# stm32_lin_router.net
KiCad netlist of a schematic drawn in EasyEDA Pro
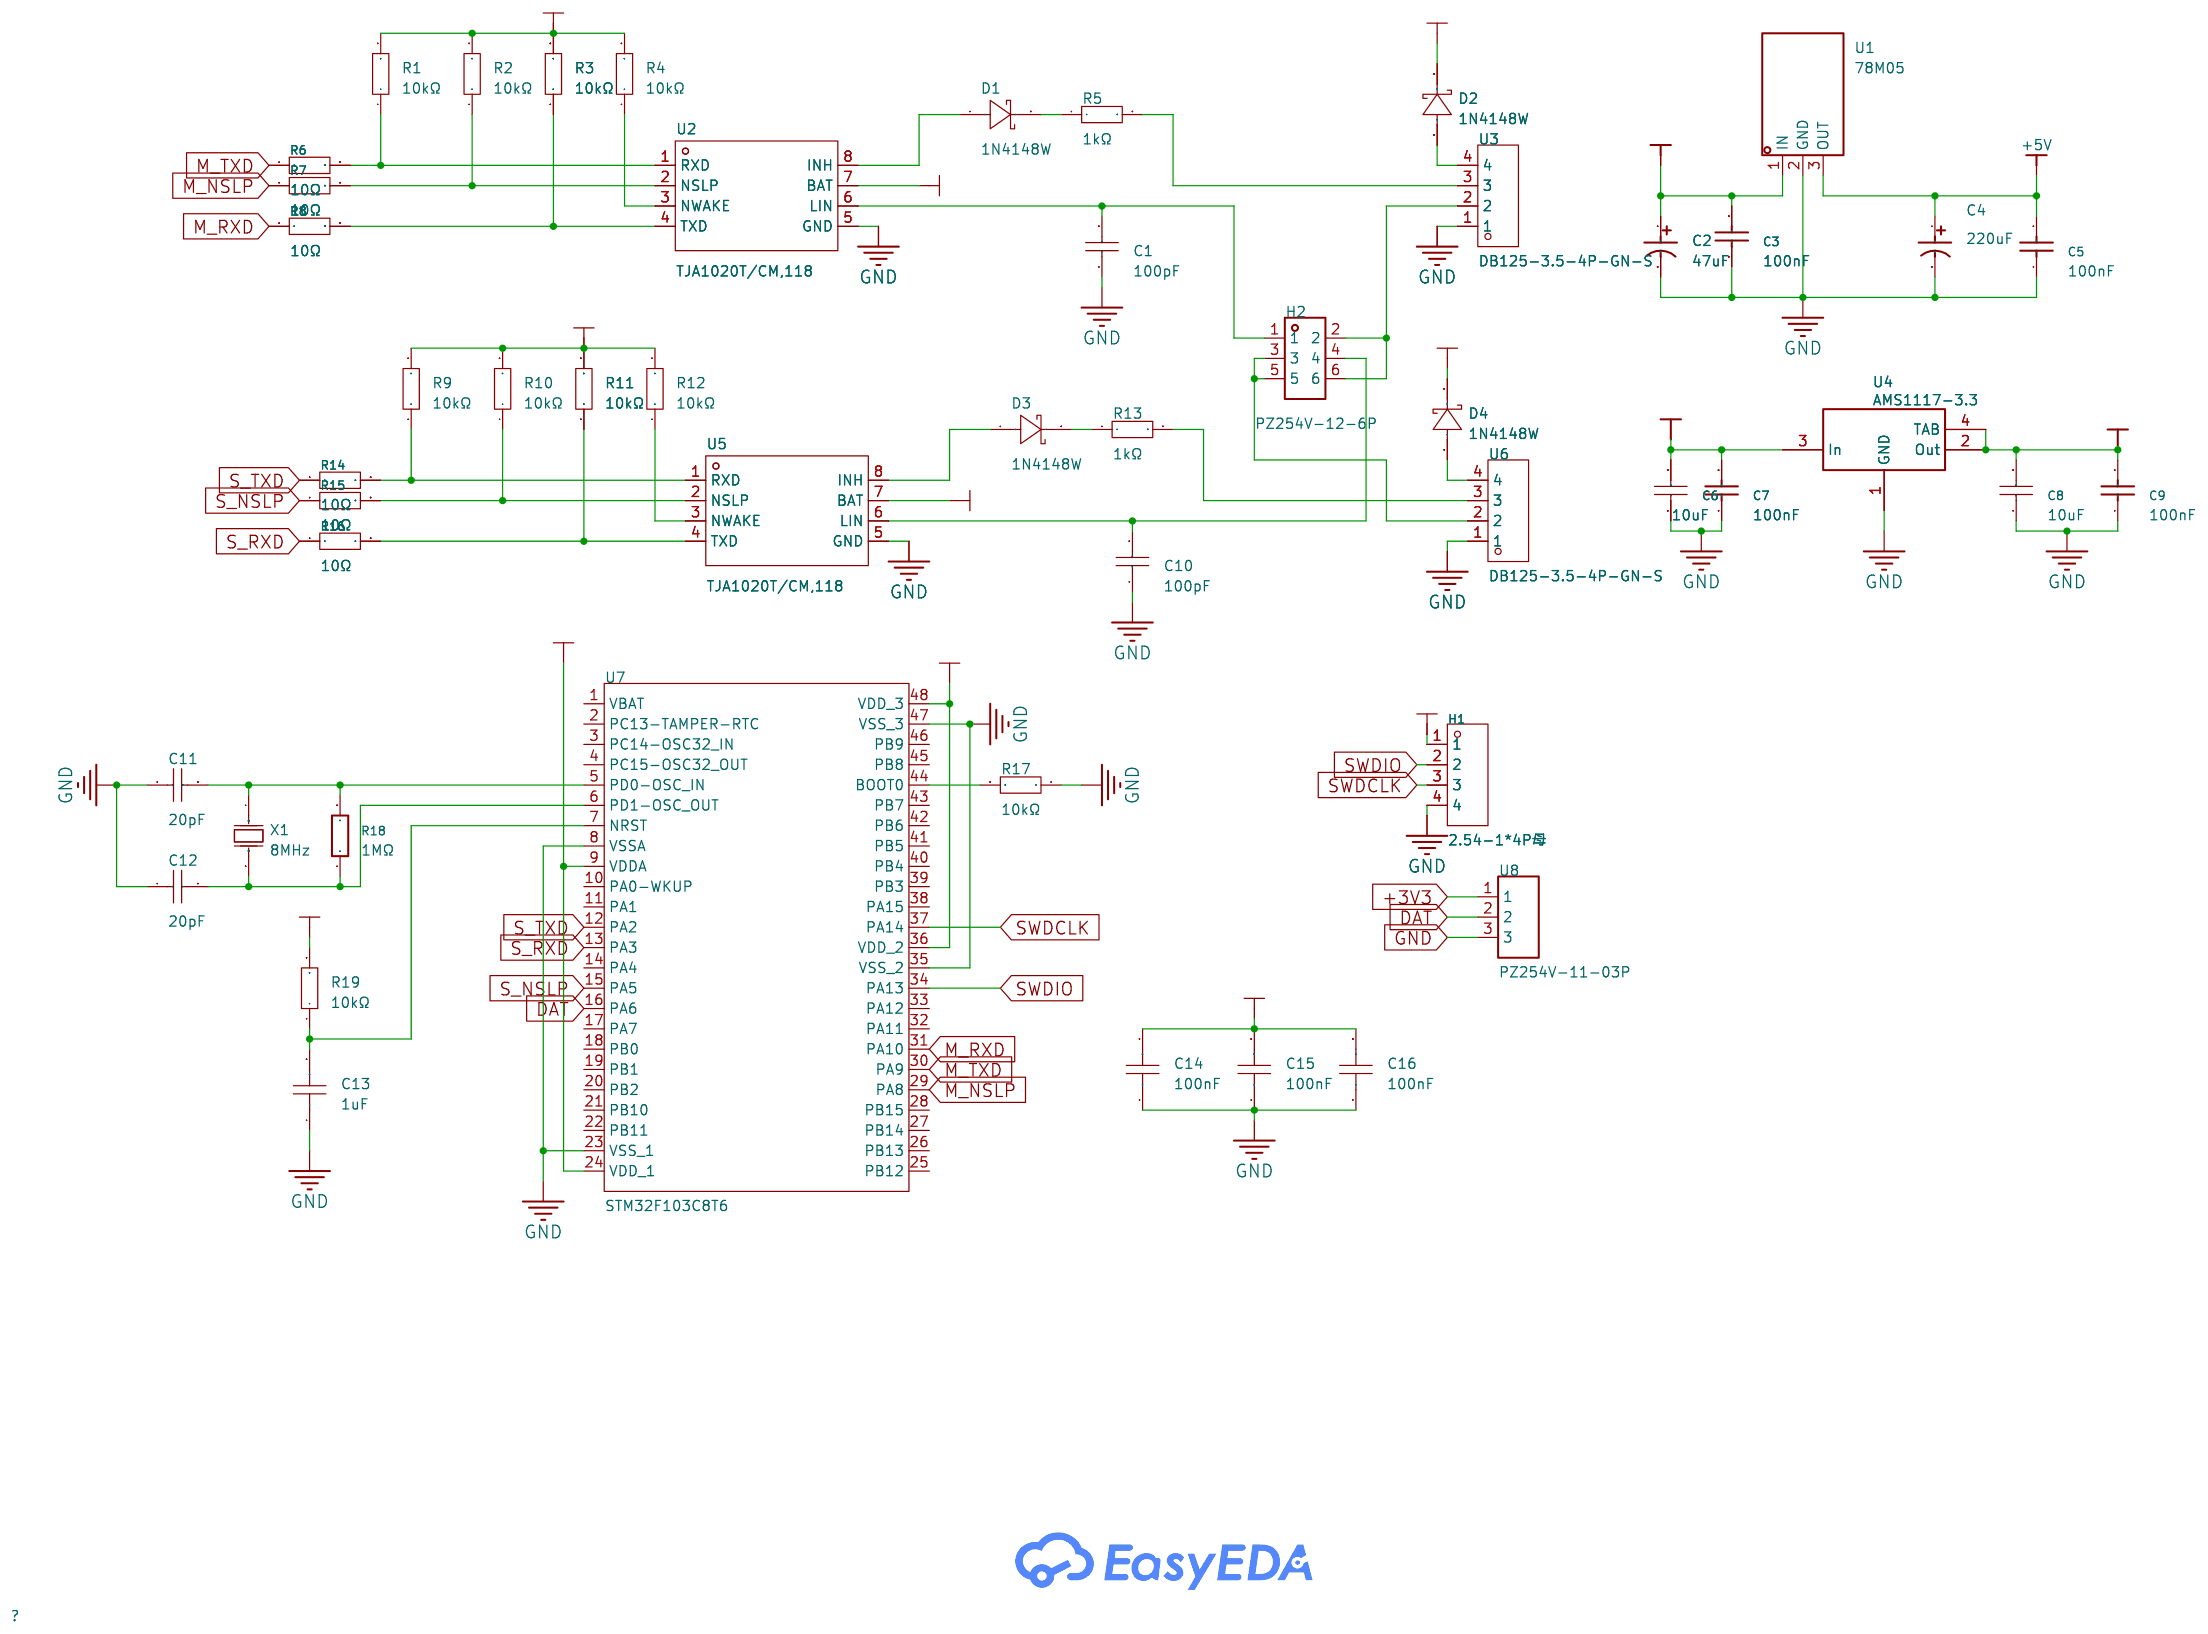
[diagram p0: schematic sheet]

(export (version "E")
  (design (tool "Eeschema 10.0.6"))
  (components
    (comp (ref "C1")
      (value "100pF")
      (description "Capacitance:100pF Tolerance:±5% Tolerance:±5% Voltage Rating:50V Temperature Coefficient:C0G")
      (fields (field (name "Manufacturer Part") "0402CG101J500NT") (field (name "Manufacturer") "FH(风华)"))
      (libsource (lib "easyedapro") (part "0402CG101J500NT"))
    )
    (comp (ref "C2")
      (value "47uF")
      (footprint "easyedapro:CAP-SMD_BD6.3-L6.6-W6.6-FD")
      (fields (field (name "Manufacturer Part") "RVT1V470M0605") (field (name "Manufacturer") "ROQANG(容强)"))
      (libsource (lib "easyedapro") (part "RVT1V470M0605_c72522"))
    )
    (comp (ref "C3")
      (value "100nF")
      (footprint "easyedapro:C0402")
      (fields
        (field (name "Manufacturer Part") "CC0402KRX7R9BB104")
        (field (name "Manufacturer") "YAGEO(国巨)")
      )
      (libsource (lib "easyedapro") (part "CC0402KRX7R9BB104"))
    )
    (comp (ref "C4")
      (value "220uF")
      (footprint "easyedapro:CAP-SMD_BD6.3-L6.6-W6.6-FD")
      (fields (field (name "Manufacturer Part") "RVT1A221M0605") (field (name "Manufacturer") "ROQANG(容强)"))
      (libsource (lib "easyedapro") (part "RVT1A221M0605-C72494"))
    )
    (comp (ref "C5")
      (value "100nF")
      (footprint "easyedapro:C0402")
      (fields
        (field (name "Manufacturer Part") "CC0402KRX7R9BB104")
        (field (name "Manufacturer") "YAGEO(国巨)")
      )
      (libsource (lib "easyedapro") (part "CC0402KRX7R9BB104"))
    )
    (comp (ref "C6")
      (value "10uF")
      (footprint "easyedapro:C0603")
      (description "Capacitance:10uF Tolerance:±20% Tolerance:±20% Voltage Rating:16V Temperature Coefficient:X5R")
      (fields
        (field (name "Manufacturer Part") "CL10A106MO8NQNC")
        (field (name "Manufacturer") "SAMSUNG(三星)")
      )
      (libsource (lib "easyedapro") (part "CL10A106MO8NQNC"))
    )
    (comp (ref "C7")
      (value "100nF")
      (footprint "easyedapro:C0402")
      (fields
        (field (name "Manufacturer Part") "CC0402KRX7R9BB104")
        (field (name "Manufacturer") "YAGEO(国巨)")
      )
      (libsource (lib "easyedapro") (part "CC0402KRX7R9BB104"))
    )
    (comp (ref "C8")
      (value "10uF")
      (footprint "easyedapro:C0603")
      (description "Capacitance:10uF Tolerance:±20% Tolerance:±20% Voltage Rating:16V Temperature Coefficient:X5R")
      (fields
        (field (name "Manufacturer Part") "CL10A106MO8NQNC")
        (field (name "Manufacturer") "SAMSUNG(三星)")
      )
      (libsource (lib "easyedapro") (part "CL10A106MO8NQNC"))
    )
    (comp (ref "C9")
      (value "100nF")
      (footprint "easyedapro:C0402")
      (fields
        (field (name "Manufacturer Part") "CC0402KRX7R9BB104")
        (field (name "Manufacturer") "YAGEO(国巨)")
      )
      (libsource (lib "easyedapro") (part "CC0402KRX7R9BB104"))
    )
    (comp (ref "C10")
      (value "100pF")
      (description "Capacitance:100pF Tolerance:±5% Tolerance:±5% Voltage Rating:50V Temperature Coefficient:C0G")
      (fields (field (name "Manufacturer Part") "0402CG101J500NT") (field (name "Manufacturer") "FH(风华)"))
      (libsource (lib "easyedapro") (part "0402CG101J500NT"))
    )
    (comp (ref "C11")
      (value "20pF")
      (footprint "easyedapro:C0402")
      (description "Capacitance:20pF Tolerance:±5% Tolerance:±5% Voltage Rating:50V Temperature Coefficient:C0G")
      (fields (field (name "Manufacturer Part") "0402CG200J500NT") (field (name "Manufacturer") "FH(风华)"))
      (libsource (lib "easyedapro") (part "0402CG200J500NT"))
    )
    (comp (ref "C12")
      (value "20pF")
      (footprint "easyedapro:C0402")
      (description "Capacitance:20pF Tolerance:±5% Tolerance:±5% Voltage Rating:50V Temperature Coefficient:C0G")
      (fields (field (name "Manufacturer Part") "0402CG200J500NT") (field (name "Manufacturer") "FH(风华)"))
      (libsource (lib "easyedapro") (part "0402CG200J500NT"))
    )
    (comp (ref "C13")
      (value "1uF")
      (footprint "easyedapro:C0402")
      (description "Capacitance:1uF Tolerance:±10% Tolerance:±10% Voltage Rating:25V Temperature Coefficient:X5R")
      (fields
        (field (name "Manufacturer Part") "CL05A105KA5NQNC")
        (field (name "Manufacturer") "SAMSUNG(三星)")
      )
      (libsource (lib "easyedapro") (part "CL05A105KA5NQNC"))
    )
    (comp (ref "C14")
      (value "100nF")
      (footprint "easyedapro:C0402")
      (description "Capacitance:100nF Tolerance:±10% Tolerance:±10% Voltage Rating:16V Temperature Coefficient:X7R")
      (fields
        (field (name "Manufacturer Part") "CL05B104KO5NNNC")
        (field (name "Manufacturer") "SAMSUNG(三星)")
      )
      (libsource (lib "easyedapro") (part "CL05B104KO5NNNC"))
    )
    (comp (ref "C15")
      (value "100nF")
      (footprint "easyedapro:C0402")
      (description "Capacitance:100nF Tolerance:±10% Tolerance:±10% Voltage Rating:16V Temperature Coefficient:X7R")
      (fields
        (field (name "Manufacturer Part") "CL05B104KO5NNNC")
        (field (name "Manufacturer") "SAMSUNG(三星)")
      )
      (libsource (lib "easyedapro") (part "CL05B104KO5NNNC"))
    )
    (comp (ref "C16")
      (value "100nF")
      (footprint "easyedapro:C0402")
      (description "Capacitance:100nF Tolerance:±10% Tolerance:±10% Voltage Rating:16V Temperature Coefficient:X7R")
      (fields
        (field (name "Manufacturer Part") "CL05B104KO5NNNC")
        (field (name "Manufacturer") "SAMSUNG(三星)")
      )
      (libsource (lib "easyedapro") (part "CL05B104KO5NNNC"))
    )
    (comp (ref "D1")
      (value "1N4148W")
      (footprint "easyedapro:SOD-123_L2.7-W1.6-LS3.7-FD")
      (fields (field (name "Manufacturer") "R+O(宏嘉诚)"))
      (libsource (lib "easyedapro") (part "1N4148W_C7420318"))
    )
    (comp (ref "D2")
      (value "1N4148W")
      (footprint "easyedapro:SOD-123_L2.7-W1.6-LS3.7-FD")
      (fields (field (name "Manufacturer") "R+O(宏嘉诚)"))
      (libsource (lib "easyedapro") (part "1N4148W_C7420318"))
    )
    (comp (ref "D3")
      (value "1N4148W")
      (footprint "easyedapro:SOD-123_L2.7-W1.6-LS3.7-FD")
      (fields (field (name "Manufacturer") "R+O(宏嘉诚)"))
      (libsource (lib "easyedapro") (part "1N4148W_C7420318"))
    )
    (comp (ref "D4")
      (value "1N4148W")
      (footprint "easyedapro:SOD-123_L2.7-W1.6-LS3.7-FD")
      (fields (field (name "Manufacturer") "R+O(宏嘉诚)"))
      (libsource (lib "easyedapro") (part "1N4148W_C7420318"))
    )
    (comp (ref "H1")
      (value "2.54-1*4P母")
      (footprint "easyedapro:HDR-TH_4P-P2.54-V-F")
      (fields (field (name "Manufacturer") "BOOMELE(博穆精密)"))
      (libsource (lib "easyedapro") (part "2.54-1*4P母"))
    )
    (comp (ref "H2")
      (value "PZ254V-12-6P")
      (footprint "easyedapro:HDR-TH_6P-P2.54-V-M-R2-C3-S2.54")
      (fields (field (name "Manufacturer") "XFCN(兴飞)"))
      (libsource (lib "easyedapro") (part "PZ254V-12-6P"))
    )
    (comp (ref "R1")
      (value "10kΩ")
      (footprint "easyedapro:R0402")
      (fields
        (field (name "Manufacturer Part") "0402WGF1002TCE")
        (field (name "Manufacturer") "UNI-ROYAL(厚声)")
      )
      (libsource (lib "easyedapro") (part "0402WGF1002TCE"))
    )
    (comp (ref "R2")
      (value "10kΩ")
      (footprint "easyedapro:R0402")
      (fields
        (field (name "Manufacturer Part") "0402WGF1002TCE")
        (field (name "Manufacturer") "UNI-ROYAL(厚声)")
      )
      (libsource (lib "easyedapro") (part "0402WGF1002TCE"))
    )
    (comp (ref "R3")
      (value "10kΩ")
      (footprint "easyedapro:R0402")
      (fields
        (field (name "Manufacturer Part") "0402WGF1002TCE")
        (field (name "Manufacturer") "UNI-ROYAL(厚声)")
      )
      (libsource (lib "easyedapro") (part "0402WGF1002TCE"))
    )
    (comp (ref "R4")
      (value "10kΩ")
      (footprint "easyedapro:R0402")
      (fields
        (field (name "Manufacturer Part") "0402WGF1002TCE")
        (field (name "Manufacturer") "UNI-ROYAL(厚声)")
      )
      (libsource (lib "easyedapro") (part "0402WGF1002TCE"))
    )
    (comp (ref "R5")
      (value "1kΩ")
      (footprint "easyedapro:R0402")
      (fields
        (field (name "Manufacturer Part") "0402WGF1001TCE")
        (field (name "Manufacturer") "UNI-ROYAL(厚声)")
      )
      (libsource (lib "easyedapro") (part "0402WGF1001TCE"))
    )
    (comp (ref "R6")
      (value "10Ω")
      (footprint "easyedapro:R0402")
      (fields
        (field (name "Manufacturer Part") "0402WGF100JTCE")
        (field (name "Manufacturer") "UNI-ROYAL(厚声)")
      )
      (libsource (lib "easyedapro") (part "0402WGF100JTCE"))
    )
    (comp (ref "R7")
      (value "10Ω")
      (footprint "easyedapro:R0402")
      (fields
        (field (name "Manufacturer Part") "0402WGF100JTCE")
        (field (name "Manufacturer") "UNI-ROYAL(厚声)")
      )
      (libsource (lib "easyedapro") (part "0402WGF100JTCE"))
    )
    (comp (ref "R8")
      (value "10Ω")
      (footprint "easyedapro:R0402")
      (fields
        (field (name "Manufacturer Part") "0402WGF100JTCE")
        (field (name "Manufacturer") "UNI-ROYAL(厚声)")
      )
      (libsource (lib "easyedapro") (part "0402WGF100JTCE"))
    )
    (comp (ref "R9")
      (value "10kΩ")
      (footprint "easyedapro:R0402")
      (fields
        (field (name "Manufacturer Part") "0402WGF1002TCE")
        (field (name "Manufacturer") "UNI-ROYAL(厚声)")
      )
      (libsource (lib "easyedapro") (part "0402WGF1002TCE"))
    )
    (comp (ref "R10")
      (value "10kΩ")
      (footprint "easyedapro:R0402")
      (fields
        (field (name "Manufacturer Part") "0402WGF1002TCE")
        (field (name "Manufacturer") "UNI-ROYAL(厚声)")
      )
      (libsource (lib "easyedapro") (part "0402WGF1002TCE"))
    )
    (comp (ref "R11")
      (value "10kΩ")
      (footprint "easyedapro:R0402")
      (fields
        (field (name "Manufacturer Part") "0402WGF1002TCE")
        (field (name "Manufacturer") "UNI-ROYAL(厚声)")
      )
      (libsource (lib "easyedapro") (part "0402WGF1002TCE"))
    )
    (comp (ref "R12")
      (value "10kΩ")
      (footprint "easyedapro:R0402")
      (fields
        (field (name "Manufacturer Part") "0402WGF1002TCE")
        (field (name "Manufacturer") "UNI-ROYAL(厚声)")
      )
      (libsource (lib "easyedapro") (part "0402WGF1002TCE"))
    )
    (comp (ref "R13")
      (value "1kΩ")
      (footprint "easyedapro:R0402")
      (fields
        (field (name "Manufacturer Part") "0402WGF1001TCE")
        (field (name "Manufacturer") "UNI-ROYAL(厚声)")
      )
      (libsource (lib "easyedapro") (part "0402WGF1001TCE"))
    )
    (comp (ref "R14")
      (value "10Ω")
      (footprint "easyedapro:R0402")
      (fields
        (field (name "Manufacturer Part") "0402WGF100JTCE")
        (field (name "Manufacturer") "UNI-ROYAL(厚声)")
      )
      (libsource (lib "easyedapro") (part "0402WGF100JTCE"))
    )
    (comp (ref "R15")
      (value "10Ω")
      (footprint "easyedapro:R0402")
      (fields
        (field (name "Manufacturer Part") "0402WGF100JTCE")
        (field (name "Manufacturer") "UNI-ROYAL(厚声)")
      )
      (libsource (lib "easyedapro") (part "0402WGF100JTCE"))
    )
    (comp (ref "R16")
      (value "10Ω")
      (footprint "easyedapro:R0402")
      (fields
        (field (name "Manufacturer Part") "0402WGF100JTCE")
        (field (name "Manufacturer") "UNI-ROYAL(厚声)")
      )
      (libsource (lib "easyedapro") (part "0402WGF100JTCE"))
    )
    (comp (ref "R17")
      (value "10kΩ")
      (footprint "easyedapro:R0402")
      (fields
        (field (name "Manufacturer Part") "0402WGF1002TCE")
        (field (name "Manufacturer") "UNI-ROYAL(厚声)")
      )
      (libsource (lib "easyedapro") (part "0402WGF1002TCE"))
    )
    (comp (ref "R18")
      (value "1MΩ")
      (footprint "easyedapro:R0402")
      (fields
        (field (name "Manufacturer Part") "0402WGF1004TCE")
        (field (name "Manufacturer") "UNI-ROYAL(厚声)")
      )
      (libsource (lib "easyedapro") (part "0402WGF1004TCE"))
    )
    (comp (ref "R19")
      (value "10kΩ")
      (footprint "easyedapro:R0402")
      (fields
        (field (name "Manufacturer Part") "0402WGF1002TCE")
        (field (name "Manufacturer") "UNI-ROYAL(厚声)")
      )
      (libsource (lib "easyedapro") (part "0402WGF1002TCE"))
    )
    (comp (ref "U1")
      (value "78M05")
      (footprint "easyedapro:TO-252-2_L6.6-W6.1-P4.57-LS9.9-BR-CW")
      (fields (field (name "Manufacturer") "UMW(友台半导体)"))
      (libsource (lib "easyedapro") (part "UMW78M05"))
    )
    (comp (ref "U2")
      (value "TJA1020T/CM,118")
      (fields (field (name "Manufacturer") "NXP(恩智浦)"))
      (libsource (lib "easyedapro") (part "TJA1020T/CM,118"))
    )
    (comp (ref "U3")
      (value "DB125-3.5-4P-GN-S")
      (footprint "easyedapro:CONN-TH_DB125-3.5-4P-GN")
      (fields (field (name "Manufacturer") "DORABO(地博电气)"))
      (libsource (lib "easyedapro") (part "DB125-3.5-4P-GN"))
    )
    (comp (ref "U4")
      (value "AMS1117-3.3")
      (fields (field (name "Manufacturer") "AMS"))
      (libsource (lib "easyedapro") (part "AMS1117-3.3"))
    )
    (comp (ref "U5")
      (value "TJA1020T/CM,118")
      (fields (field (name "Manufacturer") "NXP(恩智浦)"))
      (libsource (lib "easyedapro") (part "TJA1020T/CM,118"))
    )
    (comp (ref "U6")
      (value "DB125-3.5-4P-GN-S")
      (footprint "easyedapro:CONN-TH_DB125-3.5-4P-GN")
      (fields (field (name "Manufacturer") "DORABO(地博电气)"))
      (libsource (lib "easyedapro") (part "DB125-3.5-4P-GN"))
    )
    (comp (ref "U7")
      (value "STM32F103C8T6")
      (footprint "easyedapro:LQFP-48_L7.0-W7.0-P0.50-LS9.0-BL")
      (fields (field (name "Manufacturer") "ST(意法半导体)"))
      (libsource (lib "easyedapro") (part "STM32F103C8T6"))
    )
    (comp (ref "U8")
      (value "PZ254V-11-03P")
      (footprint "easyedapro:HDR-TH_3P-P2.54-V-M")
      (fields (field (name "Manufacturer") "XFCN(兴飞)"))
      (libsource (lib "easyedapro") (part "PZ254V-11-03P_C2937625"))
    )
    (comp (ref "X1")
      (value "8MHz")
      (footprint "easyedapro:CRYSTAL-SMD_L11.5-W4.8-LS12.7")
      (fields (field (name "Manufacturer Part") "X49SM8MSD2SC") (field (name "Manufacturer") "YXC(扬兴晶振)"))
      (libsource (lib "easyedapro") (part "X49SM8MSD2SC"))
    )
  )
  (nets
    (net (code "1") (name "+3V3") (class "Default")
      (node (ref "C14") (pin "2") (pinfunction "2_2") (pintype "unspecified"))
      (node (ref "C15") (pin "2") (pinfunction "2_2") (pintype "unspecified"))
      (node (ref "C16") (pin "2") (pinfunction "2_2") (pintype "unspecified"))
      (node (ref "C8") (pin "2") (pinfunction "2_2") (pintype "input"))
      (node (ref "C9") (pin "2") (pinfunction "2_2") (pintype "input"))
      (node (ref "H1") (pin "1") (pinfunction "1_1") (pintype "input"))
      (node (ref "R1") (pin "2") (pinfunction "2_2") (pintype "input"))
      (node (ref "R10") (pin "2") (pinfunction "2_2") (pintype "input"))
      (node (ref "R11") (pin "2") (pinfunction "2_2") (pintype "input"))
      (node (ref "R12") (pin "2") (pinfunction "2_2") (pintype "input"))
      (node (ref "R19") (pin "2") (pinfunction "2_2") (pintype "input"))
      (node (ref "R2") (pin "2") (pinfunction "2_2") (pintype "input"))
      (node (ref "R3") (pin "2") (pinfunction "2_2") (pintype "input"))
      (node (ref "R4") (pin "2") (pinfunction "2_2") (pintype "input"))
      (node (ref "R9") (pin "2") (pinfunction "2_2") (pintype "input"))
      (node (ref "U4") (pin "2") (pinfunction "Out_2") (pintype "unspecified"))
      (node (ref "U4") (pin "4") (pinfunction "TAB_4") (pintype "unspecified"))
      (node (ref "U7") (pin "24") (pinfunction "VDD_1_24") (pintype "unspecified"))
      (node (ref "U7") (pin "36") (pinfunction "VDD_2_36") (pintype "unspecified"))
      (node (ref "U7") (pin "48") (pinfunction "VDD_3_48") (pintype "unspecified"))
      (node (ref "U7") (pin "9") (pinfunction "VDDA_9") (pintype "unspecified"))
      (node (ref "U8") (pin "1") (pinfunction "1_1") (pintype "unspecified"))
    )
    (net (code "2") (name "+5V") (class "Default")
      (node (ref "C4") (pin "1") (pinfunction "1_1") (pintype "input"))
      (node (ref "C5") (pin "2") (pinfunction "2_2") (pintype "input"))
      (node (ref "C6") (pin "2") (pinfunction "2_2") (pintype "input"))
      (node (ref "C7") (pin "2") (pinfunction "2_2") (pintype "input"))
      (node (ref "U1") (pin "3") (pinfunction "OUT_3") (pintype "unspecified"))
      (node (ref "U4") (pin "3") (pinfunction "In_3") (pintype "unspecified"))
    )
    (net (code "3") (name "+12V") (class "Default")
      (node (ref "C2") (pin "1") (pinfunction "1_1") (pintype "input"))
      (node (ref "C3") (pin "2") (pinfunction "2_2") (pintype "input"))
      (node (ref "D2") (pin "2") (pinfunction "K_2") (pintype "unspecified"))
      (node (ref "U1") (pin "1") (pinfunction "IN_1") (pintype "unspecified"))
      (node (ref "U2") (pin "7") (pinfunction "BAT_7") (pintype "input"))
    )
    (net (code "4") (name "+12V_S") (class "Default")
      (node (ref "D4") (pin "2") (pinfunction "K_2") (pintype "unspecified"))
      (node (ref "U5") (pin "7") (pinfunction "BAT_7") (pintype "input"))
    )
    (net (code "5") (name "DAT") (class "Default")
      (node (ref "U7") (pin "16") (pinfunction "PA6_16") (pintype "unspecified"))
      (node (ref "U8") (pin "2") (pinfunction "2_2") (pintype "unspecified"))
    )
    (net (code "6") (name "GND") (class "Default")
      (node (ref "C1") (pin "1") (pinfunction "1_1") (pintype "input"))
      (node (ref "C10") (pin "1") (pinfunction "1_1") (pintype "input"))
      (node (ref "C11") (pin "1") (pinfunction "1_1") (pintype "input"))
      (node (ref "C12") (pin "1") (pinfunction "1_1") (pintype "input"))
      (node (ref "C13") (pin "1") (pinfunction "1_1") (pintype "unspecified"))
      (node (ref "C14") (pin "1") (pinfunction "1_1") (pintype "unspecified"))
      (node (ref "C15") (pin "1") (pinfunction "1_1") (pintype "unspecified"))
      (node (ref "C16") (pin "1") (pinfunction "1_1") (pintype "unspecified"))
      (node (ref "C2") (pin "2") (pinfunction "2_2") (pintype "input"))
      (node (ref "C3") (pin "1") (pinfunction "1_1") (pintype "input"))
      (node (ref "C4") (pin "2") (pinfunction "2_2") (pintype "input"))
      (node (ref "C5") (pin "1") (pinfunction "1_1") (pintype "input"))
      (node (ref "C6") (pin "1") (pinfunction "1_1") (pintype "input"))
      (node (ref "C7") (pin "1") (pinfunction "1_1") (pintype "input"))
      (node (ref "C8") (pin "1") (pinfunction "1_1") (pintype "input"))
      (node (ref "C9") (pin "1") (pinfunction "1_1") (pintype "input"))
      (node (ref "H1") (pin "4") (pinfunction "4_4") (pintype "input"))
      (node (ref "R17") (pin "1") (pinfunction "1_1") (pintype "input"))
      (node (ref "U1") (pin "2") (pinfunction "GND_2") (pintype "unspecified"))
      (node (ref "U2") (pin "5") (pinfunction "GND_5") (pintype "input"))
      (node (ref "U3") (pin "1") (pinfunction "1_1") (pintype "unspecified"))
      (node (ref "U4") (pin "1") (pinfunction "GND_1") (pintype "unspecified"))
      (node (ref "U5") (pin "5") (pinfunction "GND_5") (pintype "input"))
      (node (ref "U6") (pin "1") (pinfunction "1_1") (pintype "unspecified"))
      (node (ref "U7") (pin "23") (pinfunction "VSS_1_23") (pintype "unspecified"))
      (node (ref "U7") (pin "35") (pinfunction "VSS_2_35") (pintype "unspecified"))
      (node (ref "U7") (pin "47") (pinfunction "VSS_3_47") (pintype "unspecified"))
      (node (ref "U7") (pin "8") (pinfunction "VSSA_8") (pintype "unspecified"))
      (node (ref "U8") (pin "3") (pinfunction "3_3") (pintype "unspecified"))
    )
    (net (code "7") (name "M_NSLP") (class "Default")
      (node (ref "R7") (pin "1") (pinfunction "1_1") (pintype "input"))
      (node (ref "U7") (pin "29") (pinfunction "PA8_29") (pintype "unspecified"))
    )
    (net (code "8") (name "M_RXD") (class "Default")
      (node (ref "R8") (pin "1") (pinfunction "1_1") (pintype "input"))
      (node (ref "U7") (pin "31") (pinfunction "PA10_31") (pintype "unspecified"))
    )
    (net (code "9") (name "M_TXD") (class "Default")
      (node (ref "R6") (pin "1") (pinfunction "1_1") (pintype "input"))
      (node (ref "U7") (pin "30") (pinfunction "PA9_30") (pintype "unspecified"))
    )
    (net (code "10") (name "Net-(D1-A)") (class "Default")
      (node (ref "D1") (pin "1") (pinfunction "A_1") (pintype "unspecified"))
      (node (ref "U2") (pin "8") (pinfunction "INH_8") (pintype "input"))
    )
    (net (code "11") (name "Net-(D1-K)") (class "Default")
      (node (ref "D1") (pin "2") (pinfunction "K_2") (pintype "unspecified"))
      (node (ref "R5") (pin "1") (pinfunction "1_1") (pintype "input"))
    )
    (net (code "12") (name "Net-(D2-A)") (class "Default")
      (node (ref "D2") (pin "1") (pinfunction "A_1") (pintype "unspecified"))
      (node (ref "U3") (pin "4") (pinfunction "4_4") (pintype "unspecified"))
    )
    (net (code "13") (name "Net-(D3-A)") (class "Default")
      (node (ref "D3") (pin "1") (pinfunction "A_1") (pintype "unspecified"))
      (node (ref "U5") (pin "8") (pinfunction "INH_8") (pintype "input"))
    )
    (net (code "14") (name "Net-(D3-K)") (class "Default")
      (node (ref "D3") (pin "2") (pinfunction "K_2") (pintype "unspecified"))
      (node (ref "R13") (pin "1") (pinfunction "1_1") (pintype "input"))
    )
    (net (code "15") (name "Net-(D4-A)") (class "Default")
      (node (ref "D4") (pin "1") (pinfunction "A_1") (pintype "unspecified"))
      (node (ref "U6") (pin "4") (pinfunction "4_4") (pintype "unspecified"))
    )
    (net (code "16") (name "Net-(H2-Pad2)") (class "Default")
      (node (ref "H2") (pin "2") (pinfunction "2_2") (pintype "unspecified"))
      (node (ref "H2") (pin "6") (pinfunction "6_6") (pintype "unspecified"))
      (node (ref "U3") (pin "2") (pinfunction "2_2") (pintype "unspecified"))
    )
    (net (code "17") (name "Net-(H2-Pad3)") (class "Default")
      (node (ref "H2") (pin "3") (pinfunction "3_3") (pintype "unspecified"))
      (node (ref "H2") (pin "5") (pinfunction "5_5") (pintype "unspecified"))
      (node (ref "U6") (pin "2") (pinfunction "2_2") (pintype "unspecified"))
    )
    (net (code "18") (name "Net-(R5-Pad2)") (class "Default")
      (node (ref "R5") (pin "2") (pinfunction "2_2") (pintype "input"))
      (node (ref "U3") (pin "3") (pinfunction "3_3") (pintype "unspecified"))
    )
    (net (code "19") (name "Net-(R13-Pad2)") (class "Default")
      (node (ref "R13") (pin "2") (pinfunction "2_2") (pintype "input"))
      (node (ref "U6") (pin "3") (pinfunction "3_3") (pintype "unspecified"))
    )
    (net (code "20") (name "Net-(U2-LIN)") (class "Default")
      (node (ref "C1") (pin "2") (pinfunction "2_2") (pintype "input"))
      (node (ref "H2") (pin "1") (pinfunction "1_1") (pintype "unspecified"))
      (node (ref "U2") (pin "6") (pinfunction "LIN_6") (pintype "input"))
    )
    (net (code "21") (name "Net-(U2-NSLP)") (class "Default")
      (node (ref "R2") (pin "1") (pinfunction "1_1") (pintype "input"))
      (node (ref "R7") (pin "2") (pinfunction "2_2") (pintype "input"))
      (node (ref "U2") (pin "2") (pinfunction "NSLP_2") (pintype "input"))
    )
    (net (code "22") (name "Net-(U2-NWAKE)") (class "Default")
      (node (ref "R4") (pin "1") (pinfunction "1_1") (pintype "input"))
      (node (ref "U2") (pin "3") (pinfunction "NWAKE_3") (pintype "input"))
    )
    (net (code "23") (name "Net-(U2-RXD)") (class "Default")
      (node (ref "R1") (pin "1") (pinfunction "1_1") (pintype "input"))
      (node (ref "R6") (pin "2") (pinfunction "2_2") (pintype "input"))
      (node (ref "U2") (pin "1") (pinfunction "RXD_1") (pintype "input"))
    )
    (net (code "24") (name "Net-(U2-TXD)") (class "Default")
      (node (ref "R3") (pin "1") (pinfunction "1_1") (pintype "input"))
      (node (ref "R8") (pin "2") (pinfunction "2_2") (pintype "input"))
      (node (ref "U2") (pin "4") (pinfunction "TXD_4") (pintype "input"))
    )
    (net (code "25") (name "Net-(U5-LIN)") (class "Default")
      (node (ref "C10") (pin "2") (pinfunction "2_2") (pintype "input"))
      (node (ref "H2") (pin "4") (pinfunction "4_4") (pintype "unspecified"))
      (node (ref "U5") (pin "6") (pinfunction "LIN_6") (pintype "input"))
    )
    (net (code "26") (name "Net-(U5-NSLP)") (class "Default")
      (node (ref "R10") (pin "1") (pinfunction "1_1") (pintype "input"))
      (node (ref "R15") (pin "2") (pinfunction "2_2") (pintype "input"))
      (node (ref "U5") (pin "2") (pinfunction "NSLP_2") (pintype "input"))
    )
    (net (code "27") (name "Net-(U5-NWAKE)") (class "Default")
      (node (ref "R12") (pin "1") (pinfunction "1_1") (pintype "input"))
      (node (ref "U5") (pin "3") (pinfunction "NWAKE_3") (pintype "input"))
    )
    (net (code "28") (name "Net-(U5-RXD)") (class "Default")
      (node (ref "R14") (pin "2") (pinfunction "2_2") (pintype "input"))
      (node (ref "R9") (pin "1") (pinfunction "1_1") (pintype "input"))
      (node (ref "U5") (pin "1") (pinfunction "RXD_1") (pintype "input"))
    )
    (net (code "29") (name "Net-(U5-TXD)") (class "Default")
      (node (ref "R11") (pin "1") (pinfunction "1_1") (pintype "input"))
      (node (ref "R16") (pin "2") (pinfunction "2_2") (pintype "input"))
      (node (ref "U5") (pin "4") (pinfunction "TXD_4") (pintype "input"))
    )
    (net (code "30") (name "Net-(U7-BOOT0)") (class "Default")
      (node (ref "R17") (pin "2") (pinfunction "2_2") (pintype "input"))
      (node (ref "U7") (pin "44") (pinfunction "BOOT0_44") (pintype "unspecified"))
    )
    (net (code "31") (name "Net-(U7-NRST)") (class "Default")
      (node (ref "C13") (pin "2") (pinfunction "2_2") (pintype "unspecified"))
      (node (ref "R19") (pin "1") (pinfunction "1_1") (pintype "input"))
      (node (ref "U7") (pin "7") (pinfunction "NRST_7") (pintype "unspecified"))
    )
    (net (code "32") (name "Net-(U7-PD0-OSC_IN)") (class "Default")
      (node (ref "C11") (pin "2") (pinfunction "2_2") (pintype "input"))
      (node (ref "R18") (pin "2") (pinfunction "2_2") (pintype "input"))
      (node (ref "U7") (pin "5") (pinfunction "PD0-OSC_IN_5") (pintype "unspecified"))
      (node (ref "X1") (pin "1") (pinfunction "OSC1_1") (pintype "input"))
    )
    (net (code "33") (name "Net-(U7-PD1-OSC_OUT)") (class "Default")
      (node (ref "C12") (pin "2") (pinfunction "2_2") (pintype "input"))
      (node (ref "R18") (pin "1") (pinfunction "1_1") (pintype "input"))
      (node (ref "U7") (pin "6") (pinfunction "PD1-OSC_OUT_6") (pintype "unspecified"))
      (node (ref "X1") (pin "2") (pinfunction "OSC2_2") (pintype "input"))
    )
    (net (code "34") (name "SWDCLK") (class "Default")
      (node (ref "H1") (pin "3") (pinfunction "3_3") (pintype "input"))
      (node (ref "U7") (pin "37") (pinfunction "PA14_37") (pintype "unspecified"))
    )
    (net (code "35") (name "SWDIO") (class "Default")
      (node (ref "H1") (pin "2") (pinfunction "2_2") (pintype "input"))
      (node (ref "U7") (pin "34") (pinfunction "PA13_34") (pintype "unspecified"))
    )
    (net (code "36") (name "S_NSLP") (class "Default")
      (node (ref "R15") (pin "1") (pinfunction "1_1") (pintype "input"))
      (node (ref "U7") (pin "15") (pinfunction "PA5_15") (pintype "unspecified"))
    )
    (net (code "37") (name "S_RXD") (class "Default")
      (node (ref "R16") (pin "1") (pinfunction "1_1") (pintype "input"))
      (node (ref "U7") (pin "13") (pinfunction "PA3_13") (pintype "unspecified"))
    )
    (net (code "38") (name "S_TXD") (class "Default")
      (node (ref "R14") (pin "1") (pinfunction "1_1") (pintype "input"))
      (node (ref "U7") (pin "12") (pinfunction "PA2_12") (pintype "unspecified"))
    )
    (net (code "39") (name "unconnected-(U7-PA0-WKUP-Pad10)") (class "Default")
      (node (ref "U7") (pin "10") (pinfunction "PA0-WKUP_10") (pintype "unspecified"))
    )
    (net (code "40") (name "unconnected-(U7-PA1-Pad11)") (class "Default")
      (node (ref "U7") (pin "11") (pinfunction "PA1_11") (pintype "unspecified"))
    )
    (net (code "41") (name "unconnected-(U7-PA4-Pad14)") (class "Default")
      (node (ref "U7") (pin "14") (pinfunction "PA4_14") (pintype "unspecified"))
    )
    (net (code "42") (name "unconnected-(U7-PA7-Pad17)") (class "Default")
      (node (ref "U7") (pin "17") (pinfunction "PA7_17") (pintype "unspecified"))
    )
    (net (code "43") (name "unconnected-(U7-PA11-Pad32)") (class "Default")
      (node (ref "U7") (pin "32") (pinfunction "PA11_32") (pintype "unspecified"))
    )
    (net (code "44") (name "unconnected-(U7-PA12-Pad33)") (class "Default")
      (node (ref "U7") (pin "33") (pinfunction "PA12_33") (pintype "unspecified"))
    )
    (net (code "45") (name "unconnected-(U7-PA15-Pad38)") (class "Default")
      (node (ref "U7") (pin "38") (pinfunction "PA15_38") (pintype "unspecified"))
    )
    (net (code "46") (name "unconnected-(U7-PB0-Pad18)") (class "Default")
      (node (ref "U7") (pin "18") (pinfunction "PB0_18") (pintype "unspecified"))
    )
    (net (code "47") (name "unconnected-(U7-PB1-Pad19)") (class "Default")
      (node (ref "U7") (pin "19") (pinfunction "PB1_19") (pintype "unspecified"))
    )
    (net (code "48") (name "unconnected-(U7-PB2-Pad20)") (class "Default")
      (node (ref "U7") (pin "20") (pinfunction "PB2_20") (pintype "unspecified"))
    )
    (net (code "49") (name "unconnected-(U7-PB3-Pad39)") (class "Default")
      (node (ref "U7") (pin "39") (pinfunction "PB3_39") (pintype "unspecified"))
    )
    (net (code "50") (name "unconnected-(U7-PB4-Pad40)") (class "Default")
      (node (ref "U7") (pin "40") (pinfunction "PB4_40") (pintype "unspecified"))
    )
    (net (code "51") (name "unconnected-(U7-PB5-Pad41)") (class "Default")
      (node (ref "U7") (pin "41") (pinfunction "PB5_41") (pintype "unspecified"))
    )
    (net (code "52") (name "unconnected-(U7-PB6-Pad42)") (class "Default")
      (node (ref "U7") (pin "42") (pinfunction "PB6_42") (pintype "unspecified"))
    )
    (net (code "53") (name "unconnected-(U7-PB7-Pad43)") (class "Default")
      (node (ref "U7") (pin "43") (pinfunction "PB7_43") (pintype "unspecified"))
    )
    (net (code "54") (name "unconnected-(U7-PB8-Pad45)") (class "Default")
      (node (ref "U7") (pin "45") (pinfunction "PB8_45") (pintype "unspecified"))
    )
    (net (code "55") (name "unconnected-(U7-PB9-Pad46)") (class "Default")
      (node (ref "U7") (pin "46") (pinfunction "PB9_46") (pintype "unspecified"))
    )
    (net (code "56") (name "unconnected-(U7-PB10-Pad21)") (class "Default")
      (node (ref "U7") (pin "21") (pinfunction "PB10_21") (pintype "unspecified"))
    )
    (net (code "57") (name "unconnected-(U7-PB11-Pad22)") (class "Default")
      (node (ref "U7") (pin "22") (pinfunction "PB11_22") (pintype "unspecified"))
    )
    (net (code "58") (name "unconnected-(U7-PB12-Pad25)") (class "Default")
      (node (ref "U7") (pin "25") (pinfunction "PB12_25") (pintype "unspecified"))
    )
    (net (code "59") (name "unconnected-(U7-PB13-Pad26)") (class "Default")
      (node (ref "U7") (pin "26") (pinfunction "PB13_26") (pintype "unspecified"))
    )
    (net (code "60") (name "unconnected-(U7-PB14-Pad27)") (class "Default")
      (node (ref "U7") (pin "27") (pinfunction "PB14_27") (pintype "unspecified"))
    )
    (net (code "61") (name "unconnected-(U7-PB15-Pad28)") (class "Default")
      (node (ref "U7") (pin "28") (pinfunction "PB15_28") (pintype "unspecified"))
    )
    (net (code "62") (name "unconnected-(U7-PC13-TAMPER-RTC-Pad2)") (class "Default")
      (node (ref "U7") (pin "2") (pinfunction "PC13-TAMPER-RTC_2") (pintype "unspecified"))
    )
    (net (code "63") (name "unconnected-(U7-PC14-OSC32_IN-Pad3)") (class "Default")
      (node (ref "U7") (pin "3") (pinfunction "PC14-OSC32_IN_3") (pintype "unspecified"))
    )
    (net (code "64") (name "unconnected-(U7-PC15-OSC32_OUT-Pad4)") (class "Default")
      (node (ref "U7") (pin "4") (pinfunction "PC15-OSC32_OUT_4") (pintype "unspecified"))
    )
    (net (code "65") (name "unconnected-(U7-VBAT-Pad1)") (class "Default")
      (node (ref "U7") (pin "1") (pinfunction "VBAT_1") (pintype "unspecified"))
    )
  )
)
